# SheetArduinoESP32.net
KiCad netlist of a schematic drawn in Altium Designer
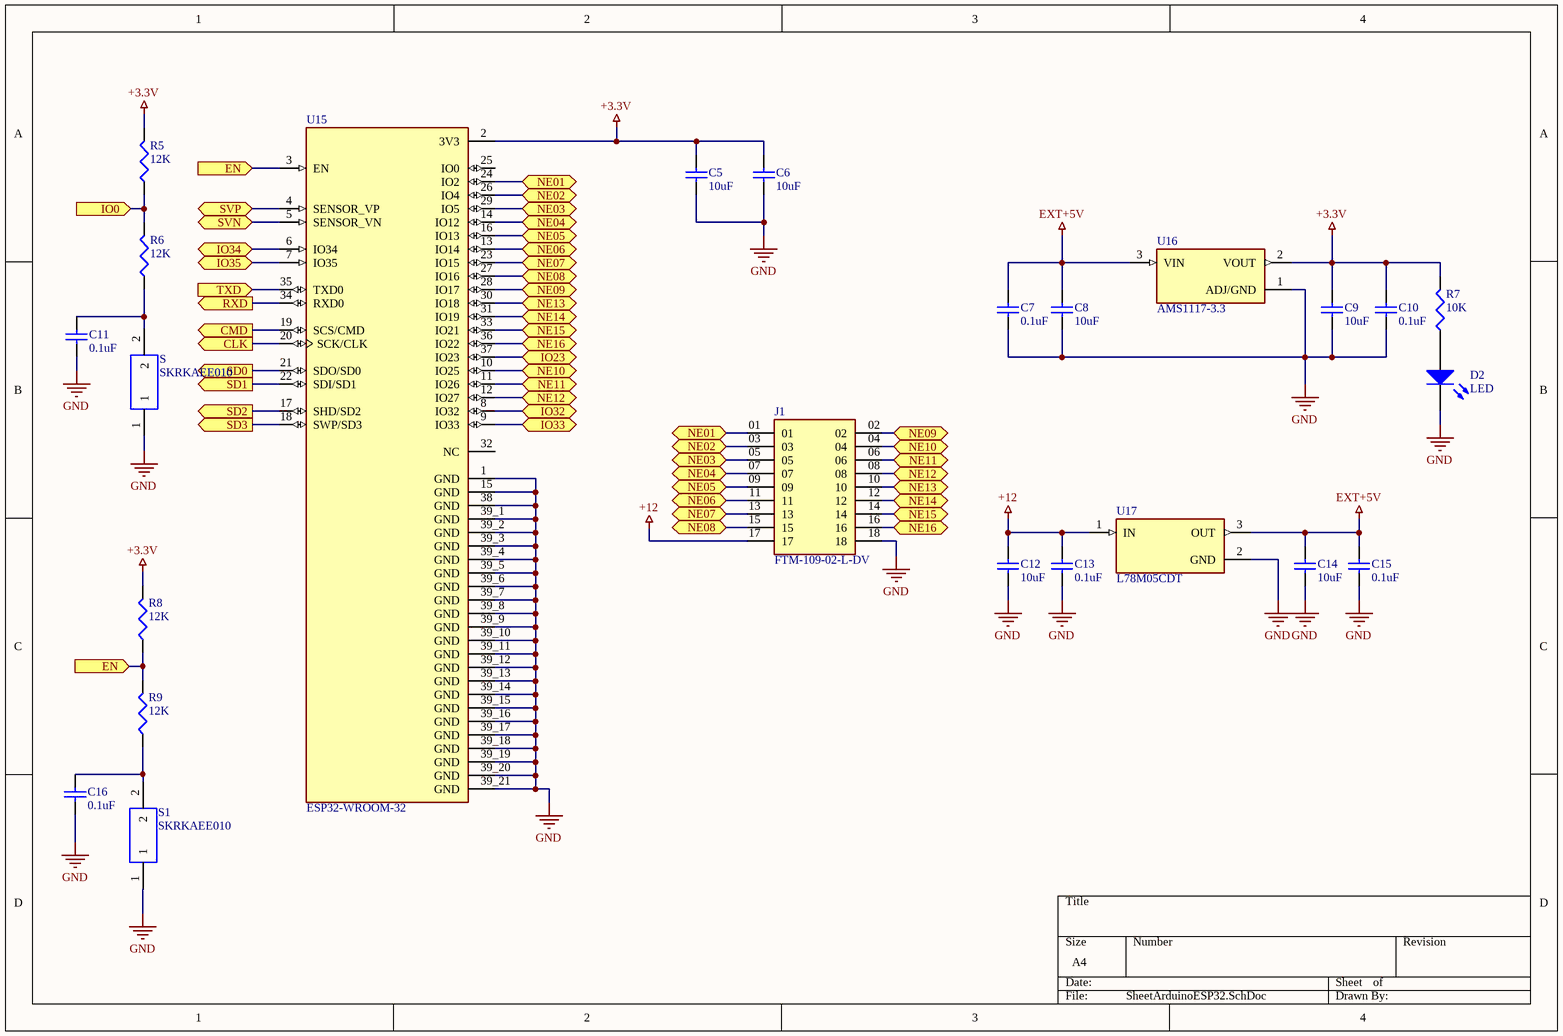
[diagram p0: SheetArduinoESP32.SchDoc]

(export (version "E")
  (design (tool "Eeschema 10.0.6"))
  (components
    (comp (ref "C5")
      (value "10uF")
      (footprint "C1206")
      (description "Capacitor (Semiconductor SIM Model)")
      (fields (field (name "PUBLISHER") "Altium Limited"))
      (libsource (lib "Miscellaneous Devices") (part "Cap Semi"))
    )
    (comp (ref "C6")
      (value "10uF")
      (footprint "C1206")
      (description "Capacitor (Semiconductor SIM Model)")
      (fields (field (name "PUBLISHER") "Altium Limited"))
      (libsource (lib "Miscellaneous Devices") (part "Cap Semi"))
    )
    (comp (ref "C7")
      (value "0.1uF")
      (footprint "1608[0603]")
      (description "Capacitor (Semiconductor SIM Model)")
      (fields (field (name "PUBLISHER") "Altium Limited"))
      (libsource (lib "Miscellaneous Devices") (part "Cap Semi"))
    )
    (comp (ref "C8")
      (value "10uF")
      (footprint "C1206")
      (description "Capacitor (Semiconductor SIM Model)")
      (fields (field (name "PUBLISHER") "Altium Limited"))
      (libsource (lib "Miscellaneous Devices") (part "Cap Semi"))
    )
    (comp (ref "C9")
      (value "10uF")
      (footprint "C1206")
      (description "Capacitor (Semiconductor SIM Model)")
      (fields (field (name "PUBLISHER") "Altium Limited"))
      (libsource (lib "Miscellaneous Devices") (part "Cap Semi"))
    )
    (comp (ref "C10")
      (value "0.1uF")
      (footprint "1608[0603]")
      (description "Capacitor (Semiconductor SIM Model)")
      (fields (field (name "PUBLISHER") "Altium Limited"))
      (libsource (lib "Miscellaneous Devices") (part "Cap Semi"))
    )
    (comp (ref "C11")
      (value "0.1uF")
      (footprint "1608[0603]")
      (description "Capacitor (Semiconductor SIM Model)")
      (fields (field (name "PUBLISHER") "Altium Limited"))
      (libsource (lib "Miscellaneous Devices") (part "Cap Semi"))
    )
    (comp (ref "C12")
      (value "10uF")
      (footprint "C1206")
      (description "Capacitor (Semiconductor SIM Model)")
      (fields (field (name "PUBLISHER") "Altium Limited"))
      (libsource (lib "Miscellaneous Devices") (part "Cap Semi"))
    )
    (comp (ref "C13")
      (value "0.1uF")
      (footprint "1608[0603]")
      (description "Capacitor (Semiconductor SIM Model)")
      (fields (field (name "PUBLISHER") "Altium Limited"))
      (libsource (lib "Miscellaneous Devices") (part "Cap Semi"))
    )
    (comp (ref "C14")
      (value "10uF")
      (footprint "C1206")
      (description "Capacitor (Semiconductor SIM Model)")
      (fields (field (name "PUBLISHER") "Altium Limited"))
      (libsource (lib "Miscellaneous Devices") (part "Cap Semi"))
    )
    (comp (ref "C15")
      (value "0.1uF")
      (footprint "1608[0603]")
      (description "Capacitor (Semiconductor SIM Model)")
      (fields (field (name "PUBLISHER") "Altium Limited"))
      (libsource (lib "Miscellaneous Devices") (part "Cap Semi"))
    )
    (comp (ref "C16")
      (value "0.1uF")
      (footprint "1608[0603]")
      (description "Capacitor (Semiconductor SIM Model)")
      (fields (field (name "PUBLISHER") "Altium Limited"))
      (libsource (lib "Miscellaneous Devices") (part "Cap Semi"))
    )
    (comp (ref "D2")
      (value "LED")
      (footprint "3.5X2.8X1.9")
      (description "Typical BLUE SiC LED")
      (fields (field (name "PUBLISHER") "Altium Limited"))
      (libsource (lib "Miscellaneous Devices") (part "LED3"))
    )
    (comp (ref "J1")
      (value "FTM-109-02-L-DV")
      (footprint "SAMTEC_FTM-109-02-L-DV")
      (libsource (lib "SMD_CON_18") (part "FTM-109-02-L-DV"))
    )
    (comp (ref "R5")
      (value "12K")
      (footprint "J1-0603")
      (description "Resistor")
      (fields (field (name "PUBLISHER") "Altium Limited"))
      (libsource (lib "Miscellaneous Devices") (part "Res3"))
    )
    (comp (ref "R6")
      (value "12K")
      (footprint "J1-0603")
      (description "Resistor")
      (fields (field (name "PUBLISHER") "Altium Limited"))
      (libsource (lib "Miscellaneous Devices") (part "Res3"))
    )
    (comp (ref "R7")
      (value "10K")
      (footprint "J1-0603")
      (description "Resistor")
      (fields (field (name "PUBLISHER") "Altium Limited"))
      (libsource (lib "Miscellaneous Devices") (part "Res3"))
    )
    (comp (ref "R8")
      (value "12K")
      (footprint "J1-0603")
      (description "Resistor")
      (fields (field (name "PUBLISHER") "Altium Limited"))
      (libsource (lib "Miscellaneous Devices") (part "Res3"))
    )
    (comp (ref "R9")
      (value "12K")
      (footprint "J1-0603")
      (description "Resistor")
      (fields (field (name "PUBLISHER") "Altium Limited"))
      (libsource (lib "Miscellaneous Devices") (part "Res3"))
    )
    (comp (ref "S")
      (value "SKRKAEE010")
      (footprint "SKRK")
      (description "Switch Tactile N.O. SPST Round Button Gull Wing 0.05A 12VDC 1.57N SMD T/R")
      (fields (field (name "MF") "ALPS"))
      (libsource (lib "Button2pin") (part "SKRKAEE010"))
    )
    (comp (ref "S1")
      (value "SKRKAEE010")
      (footprint "SKRK")
      (description "Switch Tactile N.O. SPST Round Button Gull Wing 0.05A 12VDC 1.57N SMD T/R")
      (fields (field (name "MF") "ALPS"))
      (libsource (lib "Button2pin") (part "SKRKAEE010"))
    )
    (comp (ref "U15")
      (value "ESP32-WROOM-32")
      (footprint "MODULE_ESP32-WROOM-32")
      (fields
        (field (name "MF") "Espressif Systems")
        (field (name "DIGI-KEY_PART_NUMBER") "1965-ESP32-WROOM-32U-N4CT-ND")
      )
      (libsource (lib "ESP32-WROOM-32") (part "ESP32-WROOM-32"))
    )
    (comp (ref "U16")
      (value "AMS1117-3.3")
      (footprint "SOT229P700X180-4N")
      (description "Sot223/Pkg 1-Amp 3.3-Volt Low Drop Out Voltage Regulatator")
      (fields (field (name "MF") "Advanced Monolithic Systems"))
      (libsource (lib "AMS1117-3.3") (part "AMS1117-3.3"))
    )
    (comp (ref "U17")
      (value "L78M05CDT")
      (footprint "VREG_L78M05CDT")
      (fields (field (name "MF") "STMicroelectronics"))
      (libsource (lib "L78M05CDT") (part "L78M05CDT"))
    )
  )
  (nets
    (net (code "1") (name "+3.3V") (class "Default")
      (node (ref "C10") (pin "2") (pinfunction "2_2") (pintype "passive"))
      (node (ref "C5") (pin "2") (pinfunction "2_2") (pintype "passive"))
      (node (ref "C6") (pin "2") (pinfunction "2_2") (pintype "passive"))
      (node (ref "C9") (pin "2") (pinfunction "2_2") (pintype "passive"))
      (node (ref "R5") (pin "2") (pinfunction "2_2") (pintype "passive"))
      (node (ref "R7") (pin "2") (pinfunction "2_2") (pintype "passive"))
      (node (ref "R8") (pin "2") (pinfunction "2_2") (pintype "passive"))
      (node (ref "U15") (pin "2") (pinfunction "3V3_2") (pintype "power_in"))
      (node (ref "U16") (pin "2") (pinfunction "VOUT_2") (pintype "output"))
    )
    (net (code "2") (name "+12") (class "Default")
      (node (ref "C12") (pin "2") (pinfunction "2_2") (pintype "passive"))
      (node (ref "C13") (pin "2") (pinfunction "2_2") (pintype "passive"))
      (node (ref "J1") (pin "17") (pinfunction "17_17") (pintype "passive"))
      (node (ref "U17") (pin "1") (pinfunction "IN_1") (pintype "input"))
    )
    (net (code "3") (name "/CLK") (class "Default")
      (node (ref "U15") (pin "20") (pinfunction "SCK/CLK_20") (pintype "bidirectional"))
    )
    (net (code "4") (name "/CMD") (class "Default")
      (node (ref "U15") (pin "19") (pinfunction "SCS/CMD_19") (pintype "bidirectional"))
    )
    (net (code "5") (name "/EN") (class "Default")
      (node (ref "R8") (pin "1") (pinfunction "1_1") (pintype "passive"))
      (node (ref "R9") (pin "2") (pinfunction "2_2") (pintype "passive"))
      (node (ref "U15") (pin "3") (pinfunction "EN_3") (pintype "input"))
    )
    (net (code "6") (name "/IO0") (class "Default")
      (node (ref "R5") (pin "1") (pinfunction "1_1") (pintype "passive"))
      (node (ref "R6") (pin "2") (pinfunction "2_2") (pintype "passive"))
    )
    (net (code "7") (name "/IO23") (class "Default")
      (node (ref "U15") (pin "37") (pinfunction "IO23_37") (pintype "bidirectional"))
    )
    (net (code "8") (name "/IO32") (class "Default")
      (node (ref "U15") (pin "8") (pinfunction "IO32_8") (pintype "bidirectional"))
    )
    (net (code "9") (name "/IO33") (class "Default")
      (node (ref "U15") (pin "9") (pinfunction "IO33_9") (pintype "bidirectional"))
    )
    (net (code "10") (name "/IO34") (class "Default")
      (node (ref "U15") (pin "6") (pinfunction "IO34_6") (pintype "input"))
    )
    (net (code "11") (name "/IO35") (class "Default")
      (node (ref "U15") (pin "7") (pinfunction "IO35_7") (pintype "input"))
    )
    (net (code "12") (name "/NE01") (class "Default")
      (node (ref "J1") (pin "01") (pinfunction "01_01") (pintype "passive"))
      (node (ref "U15") (pin "24") (pinfunction "IO2_24") (pintype "bidirectional"))
    )
    (net (code "13") (name "/NE02") (class "Default")
      (node (ref "J1") (pin "03") (pinfunction "03_03") (pintype "passive"))
      (node (ref "U15") (pin "26") (pinfunction "IO4_26") (pintype "bidirectional"))
    )
    (net (code "14") (name "/NE03") (class "Default")
      (node (ref "J1") (pin "05") (pinfunction "05_05") (pintype "passive"))
      (node (ref "U15") (pin "29") (pinfunction "IO5_29") (pintype "bidirectional"))
    )
    (net (code "15") (name "/NE04") (class "Default")
      (node (ref "J1") (pin "07") (pinfunction "07_07") (pintype "passive"))
      (node (ref "U15") (pin "14") (pinfunction "IO12_14") (pintype "bidirectional"))
    )
    (net (code "16") (name "/NE05") (class "Default")
      (node (ref "J1") (pin "09") (pinfunction "09_09") (pintype "passive"))
      (node (ref "U15") (pin "16") (pinfunction "IO13_16") (pintype "bidirectional"))
    )
    (net (code "17") (name "/NE06") (class "Default")
      (node (ref "J1") (pin "11") (pinfunction "11_11") (pintype "passive"))
      (node (ref "U15") (pin "13") (pinfunction "IO14_13") (pintype "bidirectional"))
    )
    (net (code "18") (name "/NE07") (class "Default")
      (node (ref "J1") (pin "13") (pinfunction "13_13") (pintype "passive"))
      (node (ref "U15") (pin "23") (pinfunction "IO15_23") (pintype "bidirectional"))
    )
    (net (code "19") (name "/NE08") (class "Default")
      (node (ref "J1") (pin "15") (pinfunction "15_15") (pintype "passive"))
      (node (ref "U15") (pin "27") (pinfunction "IO16_27") (pintype "bidirectional"))
    )
    (net (code "20") (name "/NE09") (class "Default")
      (node (ref "J1") (pin "02") (pinfunction "02_02") (pintype "passive"))
      (node (ref "U15") (pin "28") (pinfunction "IO17_28") (pintype "bidirectional"))
    )
    (net (code "21") (name "/NE10") (class "Default")
      (node (ref "J1") (pin "04") (pinfunction "04_04") (pintype "passive"))
      (node (ref "U15") (pin "10") (pinfunction "IO25_10") (pintype "bidirectional"))
    )
    (net (code "22") (name "/NE11") (class "Default")
      (node (ref "J1") (pin "06") (pinfunction "06_06") (pintype "passive"))
      (node (ref "U15") (pin "11") (pinfunction "IO26_11") (pintype "bidirectional"))
    )
    (net (code "23") (name "/NE12") (class "Default")
      (node (ref "J1") (pin "08") (pinfunction "08_08") (pintype "passive"))
      (node (ref "U15") (pin "12") (pinfunction "IO27_12") (pintype "bidirectional"))
    )
    (net (code "24") (name "/NE13") (class "Default")
      (node (ref "J1") (pin "10") (pinfunction "10_10") (pintype "passive"))
      (node (ref "U15") (pin "30") (pinfunction "IO18_30") (pintype "bidirectional"))
    )
    (net (code "25") (name "/NE14") (class "Default")
      (node (ref "J1") (pin "12") (pinfunction "12_12") (pintype "passive"))
      (node (ref "U15") (pin "31") (pinfunction "IO19_31") (pintype "bidirectional"))
    )
    (net (code "26") (name "/NE15") (class "Default")
      (node (ref "J1") (pin "14") (pinfunction "14_14") (pintype "passive"))
      (node (ref "U15") (pin "33") (pinfunction "IO21_33") (pintype "bidirectional"))
    )
    (net (code "27") (name "/NE16") (class "Default")
      (node (ref "J1") (pin "16") (pinfunction "16_16") (pintype "passive"))
      (node (ref "U15") (pin "36") (pinfunction "IO22_36") (pintype "bidirectional"))
    )
    (net (code "28") (name "/RXD") (class "Default")
      (node (ref "U15") (pin "34") (pinfunction "RXD0_34") (pintype "bidirectional"))
    )
    (net (code "29") (name "/SD0") (class "Default")
      (node (ref "U15") (pin "21") (pinfunction "SDO/SD0_21") (pintype "bidirectional"))
    )
    (net (code "30") (name "/SD1") (class "Default")
      (node (ref "U15") (pin "22") (pinfunction "SDI/SD1_22") (pintype "bidirectional"))
    )
    (net (code "31") (name "/SD2") (class "Default")
      (node (ref "U15") (pin "17") (pinfunction "SHD/SD2_17") (pintype "bidirectional"))
    )
    (net (code "32") (name "/SD3") (class "Default")
      (node (ref "U15") (pin "18") (pinfunction "SWP/SD3_18") (pintype "bidirectional"))
    )
    (net (code "33") (name "/SVN") (class "Default")
      (node (ref "U15") (pin "5") (pinfunction "SENSOR_VN_5") (pintype "input"))
    )
    (net (code "34") (name "/SVP") (class "Default")
      (node (ref "U15") (pin "4") (pinfunction "SENSOR_VP_4") (pintype "input"))
    )
    (net (code "35") (name "/TXD") (class "Default")
      (node (ref "U15") (pin "35") (pinfunction "TXD0_35") (pintype "bidirectional"))
    )
    (net (code "36") (name "EXT+5V") (class "Default")
      (node (ref "C14") (pin "2") (pinfunction "2_2") (pintype "passive"))
      (node (ref "C15") (pin "2") (pinfunction "2_2") (pintype "passive"))
      (node (ref "C7") (pin "2") (pinfunction "2_2") (pintype "passive"))
      (node (ref "C8") (pin "2") (pinfunction "2_2") (pintype "passive"))
      (node (ref "U16") (pin "3") (pinfunction "VIN_3") (pintype "input"))
      (node (ref "U17") (pin "3") (pinfunction "OUT_3") (pintype "output"))
    )
    (net (code "37") (name "GND") (class "Default")
      (node (ref "C10") (pin "1") (pinfunction "1_1") (pintype "passive"))
      (node (ref "C11") (pin "1") (pinfunction "1_1") (pintype "passive"))
      (node (ref "C12") (pin "1") (pinfunction "1_1") (pintype "passive"))
      (node (ref "C13") (pin "1") (pinfunction "1_1") (pintype "passive"))
      (node (ref "C14") (pin "1") (pinfunction "1_1") (pintype "passive"))
      (node (ref "C15") (pin "1") (pinfunction "1_1") (pintype "passive"))
      (node (ref "C16") (pin "1") (pinfunction "1_1") (pintype "passive"))
      (node (ref "C5") (pin "1") (pinfunction "1_1") (pintype "passive"))
      (node (ref "C6") (pin "1") (pinfunction "1_1") (pintype "passive"))
      (node (ref "C7") (pin "1") (pinfunction "1_1") (pintype "passive"))
      (node (ref "C8") (pin "1") (pinfunction "1_1") (pintype "passive"))
      (node (ref "C9") (pin "1") (pinfunction "1_1") (pintype "passive"))
      (node (ref "D2") (pin "2") (pinfunction "K_2") (pintype "passive"))
      (node (ref "J1") (pin "18") (pinfunction "18_18") (pintype "passive"))
      (node (ref "S") (pin "1") (pinfunction "1_1") (pintype "passive"))
      (node (ref "S1") (pin "1") (pinfunction "1_1") (pintype "passive"))
      (node (ref "U15") (pin "1") (pinfunction "GND_1") (pintype "power_in"))
      (node (ref "U15") (pin "15") (pinfunction "GND_15") (pintype "power_in"))
      (node (ref "U15") (pin "38") (pinfunction "GND_38") (pintype "power_in"))
      (node (ref "U15") (pin "39_1") (pinfunction "GND_39_1") (pintype "power_in"))
      (node (ref "U15") (pin "39_10") (pinfunction "GND_39_10") (pintype "power_in"))
      (node (ref "U15") (pin "39_11") (pinfunction "GND_39_11") (pintype "power_in"))
      (node (ref "U15") (pin "39_12") (pinfunction "GND_39_12") (pintype "power_in"))
      (node (ref "U15") (pin "39_13") (pinfunction "GND_39_13") (pintype "power_in"))
      (node (ref "U15") (pin "39_14") (pinfunction "GND_39_14") (pintype "power_in"))
      (node (ref "U15") (pin "39_15") (pinfunction "GND_39_15") (pintype "power_in"))
      (node (ref "U15") (pin "39_16") (pinfunction "GND_39_16") (pintype "power_in"))
      (node (ref "U15") (pin "39_17") (pinfunction "GND_39_17") (pintype "power_in"))
      (node (ref "U15") (pin "39_18") (pinfunction "GND_39_18") (pintype "power_in"))
      (node (ref "U15") (pin "39_19") (pinfunction "GND_39_19") (pintype "power_in"))
      (node (ref "U15") (pin "39_2") (pinfunction "GND_39_2") (pintype "power_in"))
      (node (ref "U15") (pin "39_20") (pinfunction "GND_39_20") (pintype "power_in"))
      (node (ref "U15") (pin "39_21") (pinfunction "GND_39_21") (pintype "power_in"))
      (node (ref "U15") (pin "39_3") (pinfunction "GND_39_3") (pintype "power_in"))
      (node (ref "U15") (pin "39_4") (pinfunction "GND_39_4") (pintype "power_in"))
      (node (ref "U15") (pin "39_5") (pinfunction "GND_39_5") (pintype "power_in"))
      (node (ref "U15") (pin "39_6") (pinfunction "GND_39_6") (pintype "power_in"))
      (node (ref "U15") (pin "39_7") (pinfunction "GND_39_7") (pintype "power_in"))
      (node (ref "U15") (pin "39_8") (pinfunction "GND_39_8") (pintype "power_in"))
      (node (ref "U15") (pin "39_9") (pinfunction "GND_39_9") (pintype "power_in"))
      (node (ref "U16") (pin "1") (pinfunction "ADJ/GND_1") (pintype "power_in"))
      (node (ref "U17") (pin "2") (pinfunction "GND_2") (pintype "power_in"))
    )
    (net (code "38") (name "Net-(C11-Pad2)") (class "Default")
      (node (ref "C11") (pin "2") (pinfunction "2_2") (pintype "passive"))
      (node (ref "R6") (pin "1") (pinfunction "1_1") (pintype "passive"))
      (node (ref "S") (pin "2") (pinfunction "2_2") (pintype "passive"))
    )
    (net (code "39") (name "Net-(C16-Pad2)") (class "Default")
      (node (ref "C16") (pin "2") (pinfunction "2_2") (pintype "passive"))
      (node (ref "R9") (pin "1") (pinfunction "1_1") (pintype "passive"))
      (node (ref "S1") (pin "2") (pinfunction "2_2") (pintype "passive"))
    )
    (net (code "40") (name "Net-(D2-A)") (class "Default")
      (node (ref "D2") (pin "1") (pinfunction "A_1") (pintype "passive"))
      (node (ref "R7") (pin "1") (pinfunction "1_1") (pintype "passive"))
    )
    (net (code "41") (name "unconnected-(U15-IO0-Pad25)") (class "Default")
      (node (ref "U15") (pin "25") (pinfunction "IO0_25") (pintype "bidirectional"))
    )
    (net (code "42") (name "unconnected-(U15-NC-Pad32)") (class "Default")
      (node (ref "U15") (pin "32") (pinfunction "NC_32") (pintype "passive"))
    )
  )
)
